# BLE112_Breakout_Board_v2_2.net
KiCad netlist of a schematic drawn in EAGLE
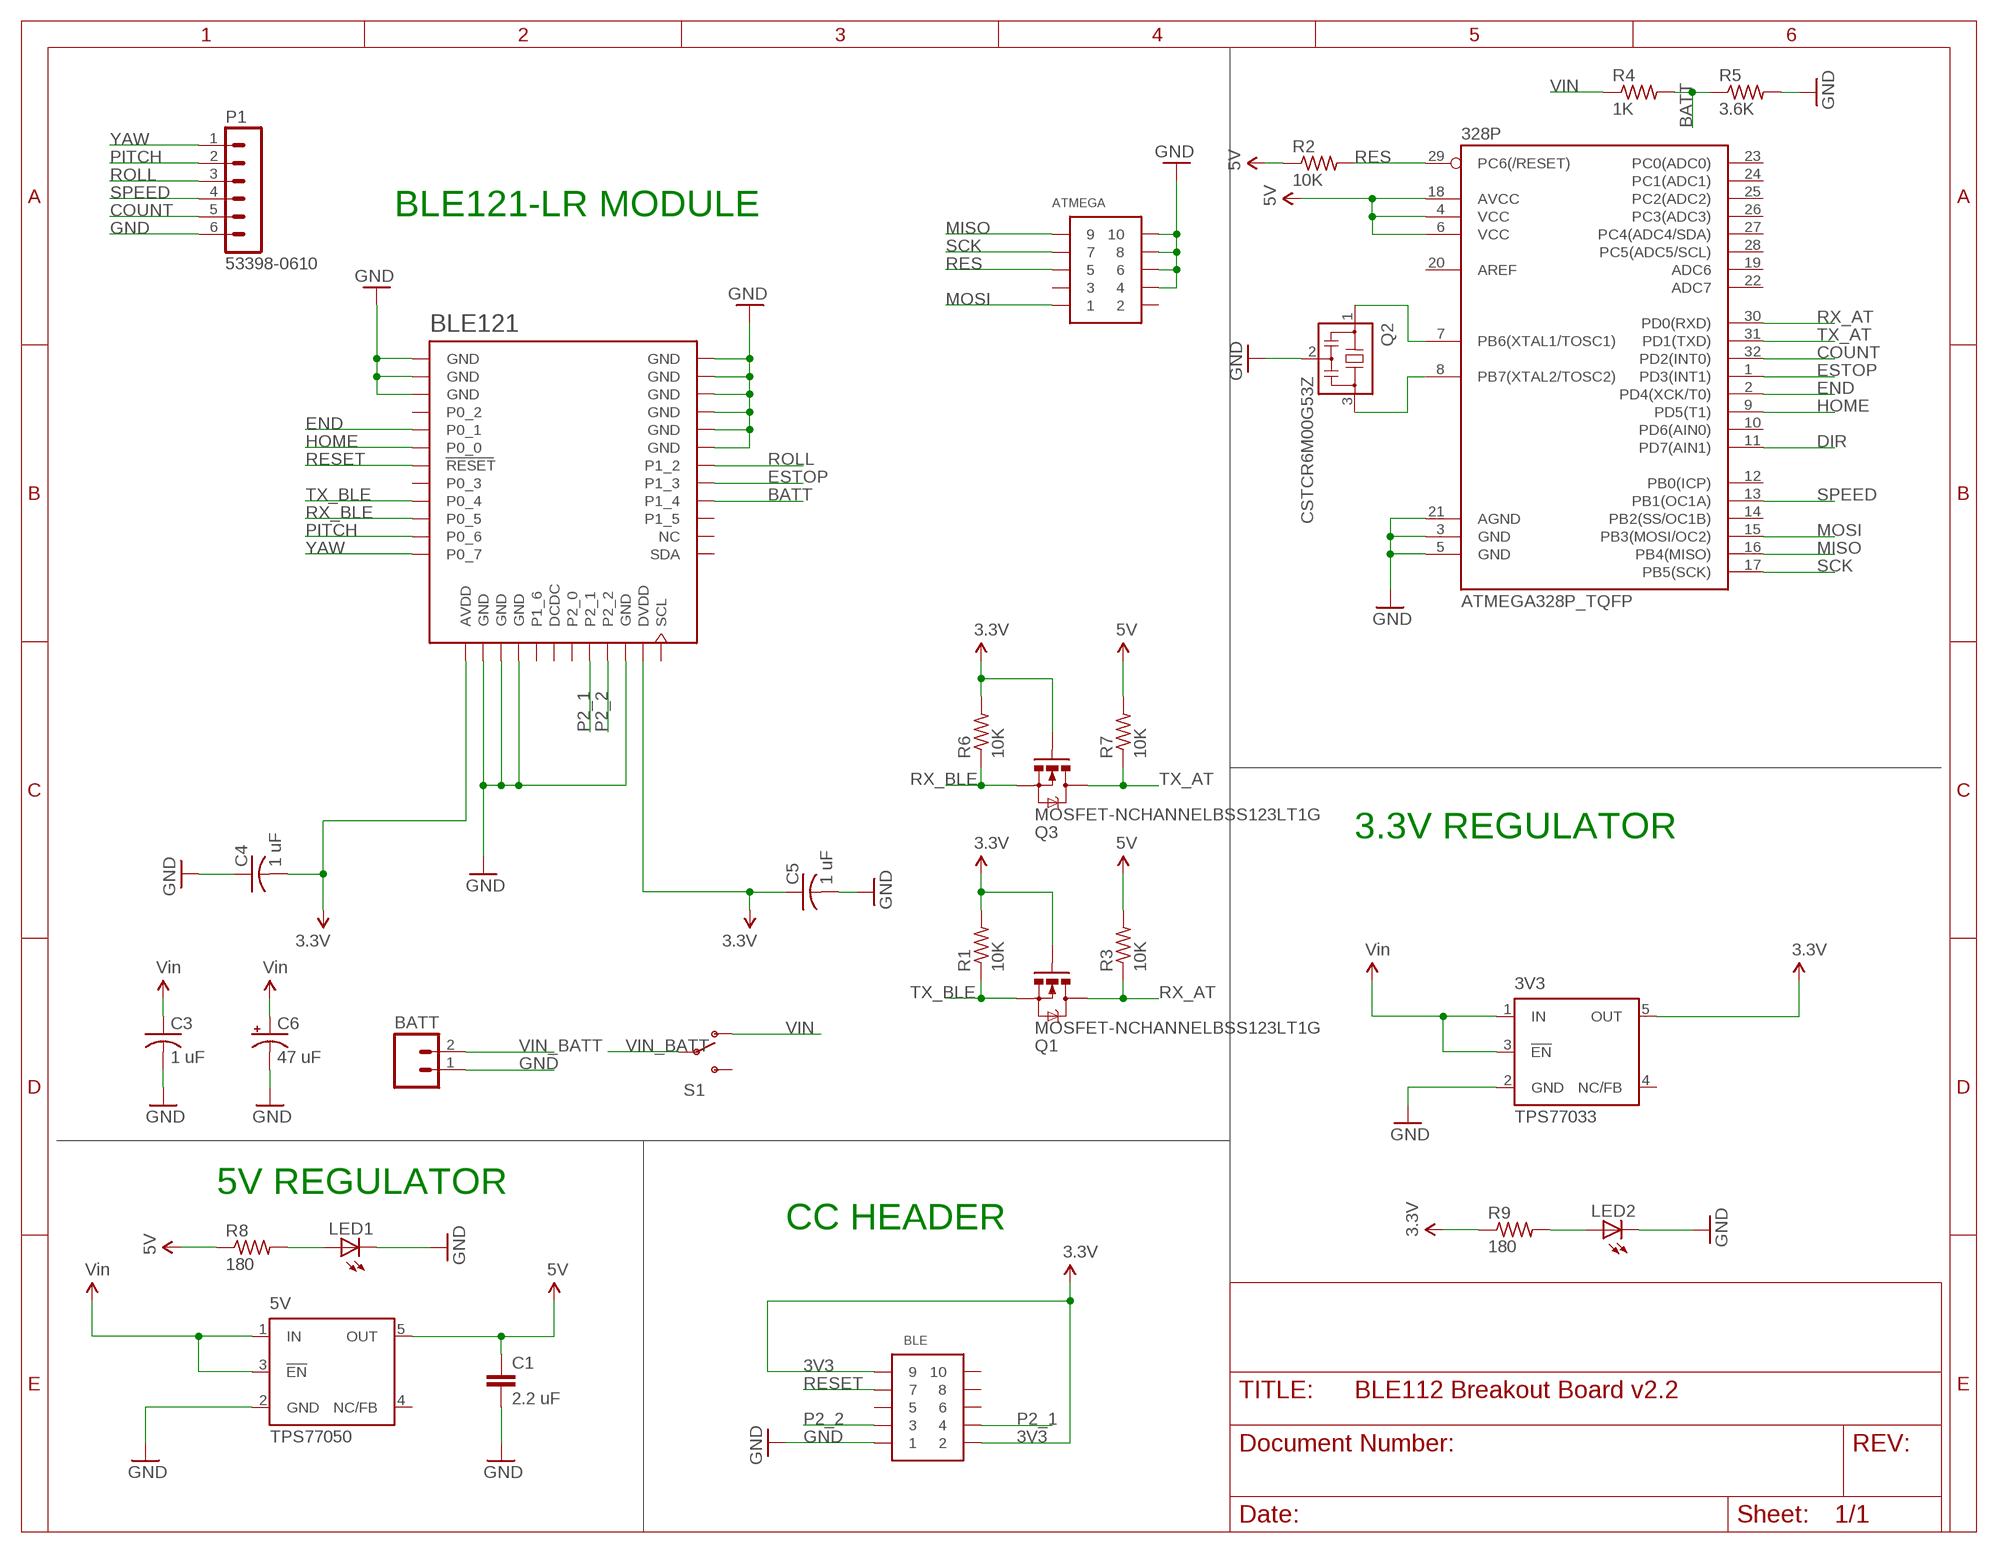
[diagram p0: schematic, sheet 1]

(export (version "E")
  (design (tool "Eeschema 10.0.6"))
  (components
    (comp (ref "3V3")
      (value "TPS77033")
      (footprint "eagle-import:SOT23-DBV")
      (fields (field (name "MF") "TEXAS INSTRUMENTS") (field (name "MPN") "TPS77033DBVT"))
      (libsource (lib "eagle-import") (part "TPS77033"))
    )
    (comp (ref "5V")
      (value "TPS77050")
      (footprint "eagle-import:SOT23-DBV")
      (fields (field (name "MF") "TEXAS INSTRUMENT CONNECTORS") (field (name "MPN") "TPS77050DBVT"))
      (libsource (lib "eagle-import") (part "TPS77050"))
    )
    (comp (ref "328P")
      (value "ATMEGA328P_TQFP")
      (footprint "eagle-import:TQFP32-08")
      (libsource (lib "eagle-import") (part "ATMEGA328P_TQFP"))
    )
    (comp (ref "ATMEGA")
      (value "CONN_5-2-FTSH-V")
      (footprint "eagle-import:FTSH-105-DV")
      (libsource (lib "eagle-import") (part "CONN_5-2-FTSH-V"))
    )
    (comp (ref "BATT")
      (value "M02JST-PTH-2")
      (footprint "eagle-import:JST-2-PTH")
      (libsource (lib "eagle-import") (part "M02JST-PTH-2"))
    )
    (comp (ref "BLE")
      (value "CONN_5-2-FTSH-V")
      (footprint "eagle-import:FTSH-105-DV")
      (libsource (lib "eagle-import") (part "CONN_5-2-FTSH-V"))
    )
    (comp (ref "BLE121")
      (value "BLE121LR-VISUAL-A")
      (footprint "eagle-import:BLE121LR-A")
      (libsource (lib "eagle-import") (part "BLE121LR-VISUAL-A"))
    )
    (comp (ref "C1")
      (value "2.2 uF")
      (footprint "eagle-import:0603-CAP")
      (libsource (lib "eagle-import") (part "CAP0603-CAP"))
    )
    (comp (ref "C3")
      (value "1 uF")
      (footprint "eagle-import:C0402")
      (libsource (lib "eagle-import") (part "C-USC0402"))
    )
    (comp (ref "C4")
      (value "1 uF")
      (footprint "eagle-import:C0402")
      (libsource (lib "eagle-import") (part "C-USC0402"))
    )
    (comp (ref "C5")
      (value "1 uF")
      (footprint "eagle-import:C0402")
      (libsource (lib "eagle-import") (part "C-USC0402"))
    )
    (comp (ref "C6")
      (value "47 uF")
      (footprint "eagle-import:PANASONIC_D")
      (libsource (lib "eagle-import") (part "CPOL-USD"))
    )
    (comp (ref "LED1")
      (value "LEDSML0603")
      (footprint "eagle-import:SML0603")
      (libsource (lib "eagle-import") (part "LEDSML0603"))
    )
    (comp (ref "LED2")
      (value "LEDSML0603")
      (footprint "eagle-import:SML0603")
      (libsource (lib "eagle-import") (part "LEDSML0603"))
    )
    (comp (ref "P1")
      (value "53398-0610")
      (footprint "eagle-import:53398-0610")
      (libsource (lib "eagle-import") (part "53398-0610"))
    )
    (comp (ref "Q1")
      (value "MOSFET-NCHANNELBSS123LT1G")
      (footprint "eagle-import:SOT23-3")
      (libsource (lib "eagle-import") (part "MOSFET-NCHANNELBSS123LT1G"))
    )
    (comp (ref "Q2")
      (value "CSTCR6M00G53Z")
      (footprint "eagle-import:CSTCR6M")
      (fields (field (name "MPN") "CSTCR6M00G53-R0"))
      (libsource (lib "eagle-import") (part "CSTCR6M00G53Z"))
    )
    (comp (ref "Q3")
      (value "MOSFET-NCHANNELBSS123LT1G")
      (footprint "eagle-import:SOT23-3")
      (libsource (lib "eagle-import") (part "MOSFET-NCHANNELBSS123LT1G"))
    )
    (comp (ref "R1")
      (value "10K")
      (footprint "eagle-import:R0402")
      (libsource (lib "eagle-import") (part "R-US_R0402"))
    )
    (comp (ref "R2")
      (value "10K")
      (footprint "eagle-import:R0402")
      (libsource (lib "eagle-import") (part "R-US_R0402"))
    )
    (comp (ref "R3")
      (value "10K")
      (footprint "eagle-import:R0402")
      (libsource (lib "eagle-import") (part "R-US_R0402"))
    )
    (comp (ref "R4")
      (value "1K")
      (footprint "eagle-import:R0402")
      (libsource (lib "eagle-import") (part "R-US_R0402"))
    )
    (comp (ref "R5")
      (value "3.6K")
      (footprint "eagle-import:R0402")
      (libsource (lib "eagle-import") (part "R-US_R0402"))
    )
    (comp (ref "R6")
      (value "10K")
      (footprint "eagle-import:R0402")
      (libsource (lib "eagle-import") (part "R-US_R0402"))
    )
    (comp (ref "R7")
      (value "10K")
      (footprint "eagle-import:R0402")
      (libsource (lib "eagle-import") (part "R-US_R0402"))
    )
    (comp (ref "R8")
      (value "180")
      (footprint "eagle-import:R0402")
      (libsource (lib "eagle-import") (part "R-US_R0402"))
    )
    (comp (ref "R9")
      (value "180")
      (footprint "eagle-import:R0402")
      (libsource (lib "eagle-import") (part "R-US_R0402"))
    )
    (comp (ref "S1")
      (value "SWITCH-SPDTSMD")
      (footprint "eagle-import:AYZ0202")
      (libsource (lib "eagle-import") (part "SWITCH-SPDTSMD"))
    )
  )
  (nets
    (net (code "1") (name "/BATT") (class "Default")
      (node (ref "BLE121") (pin "P1_4") (pinfunction "P1_4_P1_4") (pintype "bidirectional"))
      (node (ref "R4") (pin "2") (pinfunction "2_2") (pintype "passive"))
      (node (ref "R5") (pin "1") (pinfunction "1_1") (pintype "passive"))
    )
    (net (code "2") (name "/COUNT") (class "Default")
      (node (ref "328P") (pin "32") (pinfunction "PD2(INT0)_32") (pintype "bidirectional"))
      (node (ref "P1") (pin "5") (pinfunction "5_5") (pintype "passive"))
    )
    (net (code "3") (name "/DIR") (class "Default")
      (node (ref "328P") (pin "11") (pinfunction "PD7(AIN1)_11") (pintype "bidirectional"))
    )
    (net (code "4") (name "/END") (class "Default")
      (node (ref "328P") (pin "2") (pinfunction "PD4(XCK/T0)_2") (pintype "bidirectional"))
      (node (ref "BLE121") (pin "P0_1") (pinfunction "P0_1_P0_1") (pintype "bidirectional"))
    )
    (net (code "5") (name "/ESTOP") (class "Default")
      (node (ref "328P") (pin "1") (pinfunction "PD3(INT1)_1") (pintype "bidirectional"))
      (node (ref "BLE121") (pin "P1_3") (pinfunction "P1_3_P1_3") (pintype "bidirectional"))
    )
    (net (code "6") (name "/HOME") (class "Default")
      (node (ref "328P") (pin "9") (pinfunction "PD5(T1)_9") (pintype "bidirectional"))
      (node (ref "BLE121") (pin "P0_0") (pinfunction "P0_0_P0_0") (pintype "bidirectional"))
    )
    (net (code "7") (name "/MISO") (class "Default")
      (node (ref "328P") (pin "16") (pinfunction "PB4(MISO)_16") (pintype "bidirectional"))
      (node (ref "ATMEGA") (pin "9") (pinfunction "9_9") (pintype "bidirectional"))
    )
    (net (code "8") (name "/MOSI") (class "Default")
      (node (ref "328P") (pin "15") (pinfunction "PB3(MOSI/OC2)_15") (pintype "bidirectional"))
      (node (ref "ATMEGA") (pin "1") (pinfunction "1_1") (pintype "bidirectional"))
    )
    (net (code "9") (name "/P2_1") (class "Default")
      (node (ref "BLE") (pin "4") (pinfunction "4_4") (pintype "bidirectional"))
      (node (ref "BLE121") (pin "P2_1") (pinfunction "P2_1_P2_1") (pintype "bidirectional"))
    )
    (net (code "10") (name "/P2_2") (class "Default")
      (node (ref "BLE") (pin "3") (pinfunction "3_3") (pintype "bidirectional"))
      (node (ref "BLE121") (pin "P2_2") (pinfunction "P2_2_P2_2") (pintype "bidirectional"))
    )
    (net (code "11") (name "/PITCH") (class "Default")
      (node (ref "BLE121") (pin "P0_6") (pinfunction "P0_6_P0_6") (pintype "bidirectional"))
      (node (ref "P1") (pin "2") (pinfunction "2_2") (pintype "passive"))
    )
    (net (code "12") (name "/RES") (class "Default")
      (node (ref "328P") (pin "29") (pinfunction "PC6(/RESET)_29") (pintype "bidirectional"))
      (node (ref "ATMEGA") (pin "5") (pinfunction "5_5") (pintype "bidirectional"))
      (node (ref "R2") (pin "2") (pinfunction "2_2") (pintype "passive"))
    )
    (net (code "13") (name "/RESET") (class "Default")
      (node (ref "BLE") (pin "7") (pinfunction "7_7") (pintype "bidirectional"))
      (node (ref "BLE121") (pin "RESET") (pinfunction "RESET_RESET") (pintype "input"))
    )
    (net (code "14") (name "/ROLL") (class "Default")
      (node (ref "BLE121") (pin "P1_2") (pinfunction "P1_2_P1_2") (pintype "bidirectional"))
      (node (ref "P1") (pin "3") (pinfunction "3_3") (pintype "passive"))
    )
    (net (code "15") (name "/RX_AT") (class "Default")
      (node (ref "328P") (pin "30") (pinfunction "PD0(RXD)_30") (pintype "bidirectional"))
      (node (ref "Q1") (pin "3") (pinfunction "D_3") (pintype "passive"))
      (node (ref "R3") (pin "1") (pinfunction "1_1") (pintype "passive"))
    )
    (net (code "16") (name "/RX_BLE") (class "Default")
      (node (ref "BLE121") (pin "P0_5") (pinfunction "P0_5_P0_5") (pintype "bidirectional"))
      (node (ref "Q3") (pin "2") (pinfunction "S_2") (pintype "passive"))
      (node (ref "R6") (pin "1") (pinfunction "1_1") (pintype "passive"))
    )
    (net (code "17") (name "/SCK") (class "Default")
      (node (ref "328P") (pin "17") (pinfunction "PB5(SCK)_17") (pintype "bidirectional"))
      (node (ref "ATMEGA") (pin "7") (pinfunction "7_7") (pintype "bidirectional"))
    )
    (net (code "18") (name "/SPEED") (class "Default")
      (node (ref "328P") (pin "13") (pinfunction "PB1(OC1A)_13") (pintype "bidirectional"))
      (node (ref "P1") (pin "4") (pinfunction "4_4") (pintype "passive"))
    )
    (net (code "19") (name "/TX_AT") (class "Default")
      (node (ref "328P") (pin "31") (pinfunction "PD1(TXD)_31") (pintype "bidirectional"))
      (node (ref "Q3") (pin "3") (pinfunction "D_3") (pintype "passive"))
      (node (ref "R7") (pin "1") (pinfunction "1_1") (pintype "passive"))
    )
    (net (code "20") (name "/TX_BLE") (class "Default")
      (node (ref "BLE121") (pin "P0_4") (pinfunction "P0_4_P0_4") (pintype "bidirectional"))
      (node (ref "Q1") (pin "2") (pinfunction "S_2") (pintype "passive"))
      (node (ref "R1") (pin "1") (pinfunction "1_1") (pintype "passive"))
    )
    (net (code "21") (name "/VIN_BATT") (class "Default")
      (node (ref "BATT") (pin "2") (pinfunction "2_2") (pintype "passive"))
      (node (ref "S1") (pin "2") (pinfunction "P_2") (pintype "passive"))
    )
    (net (code "22") (name "/YAW") (class "Default")
      (node (ref "BLE121") (pin "P0_7") (pinfunction "P0_7_P0_7") (pintype "bidirectional"))
      (node (ref "P1") (pin "1") (pinfunction "1_1") (pintype "passive"))
    )
    (net (code "23") (name "3.3V") (class "Default")
      (node (ref "3V3") (pin "5") (pinfunction "OUT_5") (pintype "passive"))
      (node (ref "BLE") (pin "2") (pinfunction "2_2") (pintype "bidirectional"))
      (node (ref "BLE") (pin "9") (pinfunction "9_9") (pintype "bidirectional"))
      (node (ref "BLE121") (pin "AVDD") (pinfunction "AVDD_AVDD") (pintype "power_in"))
      (node (ref "BLE121") (pin "DVDD") (pinfunction "DVDD_DVDD") (pintype "power_in"))
      (node (ref "C4") (pin "2") (pinfunction "2_2") (pintype "passive"))
      (node (ref "C5") (pin "1") (pinfunction "1_1") (pintype "passive"))
      (node (ref "Q1") (pin "1") (pinfunction "G_1") (pintype "passive"))
      (node (ref "Q3") (pin "1") (pinfunction "G_1") (pintype "passive"))
      (node (ref "R1") (pin "2") (pinfunction "2_2") (pintype "passive"))
      (node (ref "R6") (pin "2") (pinfunction "2_2") (pintype "passive"))
      (node (ref "R9") (pin "1") (pinfunction "1_1") (pintype "passive"))
    )
    (net (code "24") (name "5V") (class "Default")
      (node (ref "328P") (pin "18") (pinfunction "AVCC_18") (pintype "bidirectional"))
      (node (ref "328P") (pin "4") (pinfunction "VCC_4") (pintype "bidirectional"))
      (node (ref "328P") (pin "6") (pinfunction "VCC_6") (pintype "bidirectional"))
      (node (ref "5V") (pin "5") (pinfunction "OUT_5") (pintype "passive"))
      (node (ref "C1") (pin "1") (pinfunction "1_1") (pintype "passive"))
      (node (ref "R2") (pin "1") (pinfunction "1_1") (pintype "passive"))
      (node (ref "R3") (pin "2") (pinfunction "2_2") (pintype "passive"))
      (node (ref "R7") (pin "2") (pinfunction "2_2") (pintype "passive"))
      (node (ref "R8") (pin "1") (pinfunction "1_1") (pintype "passive"))
    )
    (net (code "25") (name "GND") (class "Default")
      (node (ref "328P") (pin "21") (pinfunction "AGND_21") (pintype "bidirectional"))
      (node (ref "328P") (pin "3") (pinfunction "GND_3") (pintype "bidirectional"))
      (node (ref "328P") (pin "5") (pinfunction "GND_5") (pintype "bidirectional"))
      (node (ref "3V3") (pin "2") (pinfunction "GND_2") (pintype "power_in"))
      (node (ref "5V") (pin "2") (pinfunction "GND_2") (pintype "power_in"))
      (node (ref "ATMEGA") (pin "10") (pinfunction "10_10") (pintype "bidirectional"))
      (node (ref "ATMEGA") (pin "4") (pinfunction "4_4") (pintype "bidirectional"))
      (node (ref "ATMEGA") (pin "6") (pinfunction "6_6") (pintype "bidirectional"))
      (node (ref "ATMEGA") (pin "8") (pinfunction "8_8") (pintype "bidirectional"))
      (node (ref "BATT") (pin "1") (pinfunction "1_1") (pintype "passive"))
      (node (ref "BLE") (pin "1") (pinfunction "1_1") (pintype "bidirectional"))
      (node (ref "BLE121") (pin "GND") (pinfunction "GND_GND") (pintype "power_in"))
      (node (ref "BLE121") (pin "GND@10") (pinfunction "GND_GND@10") (pintype "power_in"))
      (node (ref "BLE121") (pin "GND@11") (pinfunction "GND_GND@11") (pintype "power_in"))
      (node (ref "BLE121") (pin "GND@12") (pinfunction "GND_GND@12") (pintype "power_in"))
      (node (ref "BLE121") (pin "GND@13") (pinfunction "GND_GND@13") (pintype "power_in"))
      (node (ref "BLE121") (pin "GND@2") (pinfunction "GND_GND@2") (pintype "power_in"))
      (node (ref "BLE121") (pin "GND@3") (pinfunction "GND_GND@3") (pintype "power_in"))
      (node (ref "BLE121") (pin "GND@4") (pinfunction "GND_GND@4") (pintype "power_in"))
      (node (ref "BLE121") (pin "GND@5") (pinfunction "GND_GND@5") (pintype "power_in"))
      (node (ref "BLE121") (pin "GND@6") (pinfunction "GND_GND@6") (pintype "power_in"))
      (node (ref "BLE121") (pin "GND@7") (pinfunction "GND_GND@7") (pintype "power_in"))
      (node (ref "BLE121") (pin "GND@8") (pinfunction "GND_GND@8") (pintype "power_in"))
      (node (ref "BLE121") (pin "GND@9") (pinfunction "GND_GND@9") (pintype "power_in"))
      (node (ref "C1") (pin "2") (pinfunction "2_2") (pintype "passive"))
      (node (ref "C3") (pin "2") (pinfunction "2_2") (pintype "passive"))
      (node (ref "C4") (pin "1") (pinfunction "1_1") (pintype "passive"))
      (node (ref "C5") (pin "2") (pinfunction "2_2") (pintype "passive"))
      (node (ref "C6") (pin "-") (pinfunction "-_-") (pintype "passive"))
      (node (ref "LED1") (pin "C") (pinfunction "C_C") (pintype "passive"))
      (node (ref "LED2") (pin "C") (pinfunction "C_C") (pintype "passive"))
      (node (ref "P1") (pin "6") (pinfunction "6_6") (pintype "passive"))
      (node (ref "Q2") (pin "2") (pinfunction "2_2") (pintype "passive"))
      (node (ref "R5") (pin "2") (pinfunction "2_2") (pintype "passive"))
    )
    (net (code "26") (name "Net-(328P-PB6(XTAL1{slash}TOSC1))") (class "Default")
      (node (ref "328P") (pin "7") (pinfunction "PB6(XTAL1/TOSC1)_7") (pintype "bidirectional"))
      (node (ref "Q2") (pin "1") (pinfunction "1_1") (pintype "passive"))
    )
    (net (code "27") (name "Net-(328P-PB7(XTAL2{slash}TOSC2))") (class "Default")
      (node (ref "328P") (pin "8") (pinfunction "PB7(XTAL2/TOSC2)_8") (pintype "bidirectional"))
      (node (ref "Q2") (pin "3") (pinfunction "3_3") (pintype "passive"))
    )
    (net (code "28") (name "Net-(LED1-PadA)") (class "Default")
      (node (ref "LED1") (pin "A") (pinfunction "A_A") (pintype "passive"))
      (node (ref "R8") (pin "2") (pinfunction "2_2") (pintype "passive"))
    )
    (net (code "29") (name "Net-(LED2-PadA)") (class "Default")
      (node (ref "LED2") (pin "A") (pinfunction "A_A") (pintype "passive"))
      (node (ref "R9") (pin "2") (pinfunction "2_2") (pintype "passive"))
    )
    (net (code "30") (name "Vin") (class "Default")
      (node (ref "3V3") (pin "1") (pinfunction "IN_1") (pintype "input"))
      (node (ref "3V3") (pin "3") (pinfunction "~{EN}_3") (pintype "input"))
      (node (ref "5V") (pin "1") (pinfunction "IN_1") (pintype "input"))
      (node (ref "5V") (pin "3") (pinfunction "~{EN}_3") (pintype "input"))
      (node (ref "C3") (pin "1") (pinfunction "1_1") (pintype "passive"))
      (node (ref "C6") (pin "+") (pinfunction "+_+") (pintype "passive"))
      (node (ref "R4") (pin "1") (pinfunction "1_1") (pintype "passive"))
      (node (ref "S1") (pin "1") (pinfunction "O_1") (pintype "passive"))
    )
    (net (code "31") (name "unconnected-(3V3-NC{slash}FB-Pad4)") (class "Default")
      (node (ref "3V3") (pin "4") (pinfunction "NC/FB_4") (pintype "passive"))
    )
    (net (code "32") (name "unconnected-(5V-NC{slash}FB-Pad4)") (class "Default")
      (node (ref "5V") (pin "4") (pinfunction "NC/FB_4") (pintype "passive"))
    )
    (net (code "33") (name "unconnected-(328P-ADC6-Pad19)") (class "Default")
      (node (ref "328P") (pin "19") (pinfunction "ADC6_19") (pintype "bidirectional"))
    )
    (net (code "34") (name "unconnected-(328P-ADC7-Pad22)") (class "Default")
      (node (ref "328P") (pin "22") (pinfunction "ADC7_22") (pintype "bidirectional"))
    )
    (net (code "35") (name "unconnected-(328P-AREF-Pad20)") (class "Default")
      (node (ref "328P") (pin "20") (pinfunction "AREF_20") (pintype "bidirectional"))
    )
    (net (code "36") (name "unconnected-(328P-PB0(ICP)-Pad12)") (class "Default")
      (node (ref "328P") (pin "12") (pinfunction "PB0(ICP)_12") (pintype "bidirectional"))
    )
    (net (code "37") (name "unconnected-(328P-PB2(SS{slash}OC1B)-Pad14)") (class "Default")
      (node (ref "328P") (pin "14") (pinfunction "PB2(SS/OC1B)_14") (pintype "bidirectional"))
    )
    (net (code "38") (name "unconnected-(328P-PC0(ADC0)-Pad23)") (class "Default")
      (node (ref "328P") (pin "23") (pinfunction "PC0(ADC0)_23") (pintype "bidirectional"))
    )
    (net (code "39") (name "unconnected-(328P-PC1(ADC1)-Pad24)") (class "Default")
      (node (ref "328P") (pin "24") (pinfunction "PC1(ADC1)_24") (pintype "bidirectional"))
    )
    (net (code "40") (name "unconnected-(328P-PC2(ADC2)-Pad25)") (class "Default")
      (node (ref "328P") (pin "25") (pinfunction "PC2(ADC2)_25") (pintype "bidirectional"))
    )
    (net (code "41") (name "unconnected-(328P-PC3(ADC3)-Pad26)") (class "Default")
      (node (ref "328P") (pin "26") (pinfunction "PC3(ADC3)_26") (pintype "bidirectional"))
    )
    (net (code "42") (name "unconnected-(328P-PC4(ADC4{slash}SDA)-Pad27)") (class "Default")
      (node (ref "328P") (pin "27") (pinfunction "PC4(ADC4/SDA)_27") (pintype "bidirectional"))
    )
    (net (code "43") (name "unconnected-(328P-PC5(ADC5{slash}SCL)-Pad28)") (class "Default")
      (node (ref "328P") (pin "28") (pinfunction "PC5(ADC5/SCL)_28") (pintype "bidirectional"))
    )
    (net (code "44") (name "unconnected-(328P-PD6(AIN0)-Pad10)") (class "Default")
      (node (ref "328P") (pin "10") (pinfunction "PD6(AIN0)_10") (pintype "bidirectional"))
    )
    (net (code "45") (name "unconnected-(ATMEGA-Pad2)") (class "Default")
      (node (ref "ATMEGA") (pin "2") (pinfunction "2_2") (pintype "bidirectional"))
    )
    (net (code "46") (name "unconnected-(ATMEGA-Pad3)") (class "Default")
      (node (ref "ATMEGA") (pin "3") (pinfunction "3_3") (pintype "bidirectional"))
    )
    (net (code "47") (name "unconnected-(BLE-Pad5)") (class "Default")
      (node (ref "BLE") (pin "5") (pinfunction "5_5") (pintype "bidirectional"))
    )
    (net (code "48") (name "unconnected-(BLE-Pad6)") (class "Default")
      (node (ref "BLE") (pin "6") (pinfunction "6_6") (pintype "bidirectional"))
    )
    (net (code "49") (name "unconnected-(BLE-Pad8)") (class "Default")
      (node (ref "BLE") (pin "8") (pinfunction "8_8") (pintype "bidirectional"))
    )
    (net (code "50") (name "unconnected-(BLE-Pad10)") (class "Default")
      (node (ref "BLE") (pin "10") (pinfunction "10_10") (pintype "bidirectional"))
    )
    (net (code "51") (name "unconnected-(BLE121-PadDCDC)") (class "Default")
      (node (ref "BLE121") (pin "DCDC") (pinfunction "DCDC_DCDC") (pintype "bidirectional"))
    )
    (net (code "52") (name "unconnected-(BLE121-PadNC)") (class "Default")
      (node (ref "BLE121") (pin "NC") (pinfunction "NC_NC") (pintype "no_connect"))
    )
    (net (code "53") (name "unconnected-(BLE121-PadP0_2)") (class "Default")
      (node (ref "BLE121") (pin "P0_2") (pinfunction "P0_2_P0_2") (pintype "bidirectional"))
    )
    (net (code "54") (name "unconnected-(BLE121-PadP0_3)") (class "Default")
      (node (ref "BLE121") (pin "P0_3") (pinfunction "P0_3_P0_3") (pintype "bidirectional"))
    )
    (net (code "55") (name "unconnected-(BLE121-PadP1_5)") (class "Default")
      (node (ref "BLE121") (pin "P1_5") (pinfunction "P1_5_P1_5") (pintype "bidirectional"))
    )
    (net (code "56") (name "unconnected-(BLE121-PadP1_6)") (class "Default")
      (node (ref "BLE121") (pin "P1_6") (pinfunction "P1_6_P1_6") (pintype "bidirectional"))
    )
    (net (code "57") (name "unconnected-(BLE121-PadP2_0)") (class "Default")
      (node (ref "BLE121") (pin "P2_0") (pinfunction "P2_0_P2_0") (pintype "bidirectional"))
    )
    (net (code "58") (name "unconnected-(BLE121-PadSCL)") (class "Default")
      (node (ref "BLE121") (pin "SCL") (pinfunction "SCL_SCL") (pintype "bidirectional"))
    )
    (net (code "59") (name "unconnected-(BLE121-PadSDA)") (class "Default")
      (node (ref "BLE121") (pin "SDA") (pinfunction "SDA_SDA") (pintype "bidirectional"))
    )
    (net (code "60") (name "unconnected-(S1-S-Pad3)") (class "Default")
      (node (ref "S1") (pin "3") (pinfunction "S_3") (pintype "passive"))
    )
  )
)
